# SCH_1-Up-Hackpad_2025-02-28.net
KiCad netlist of a schematic drawn in EasyEDA
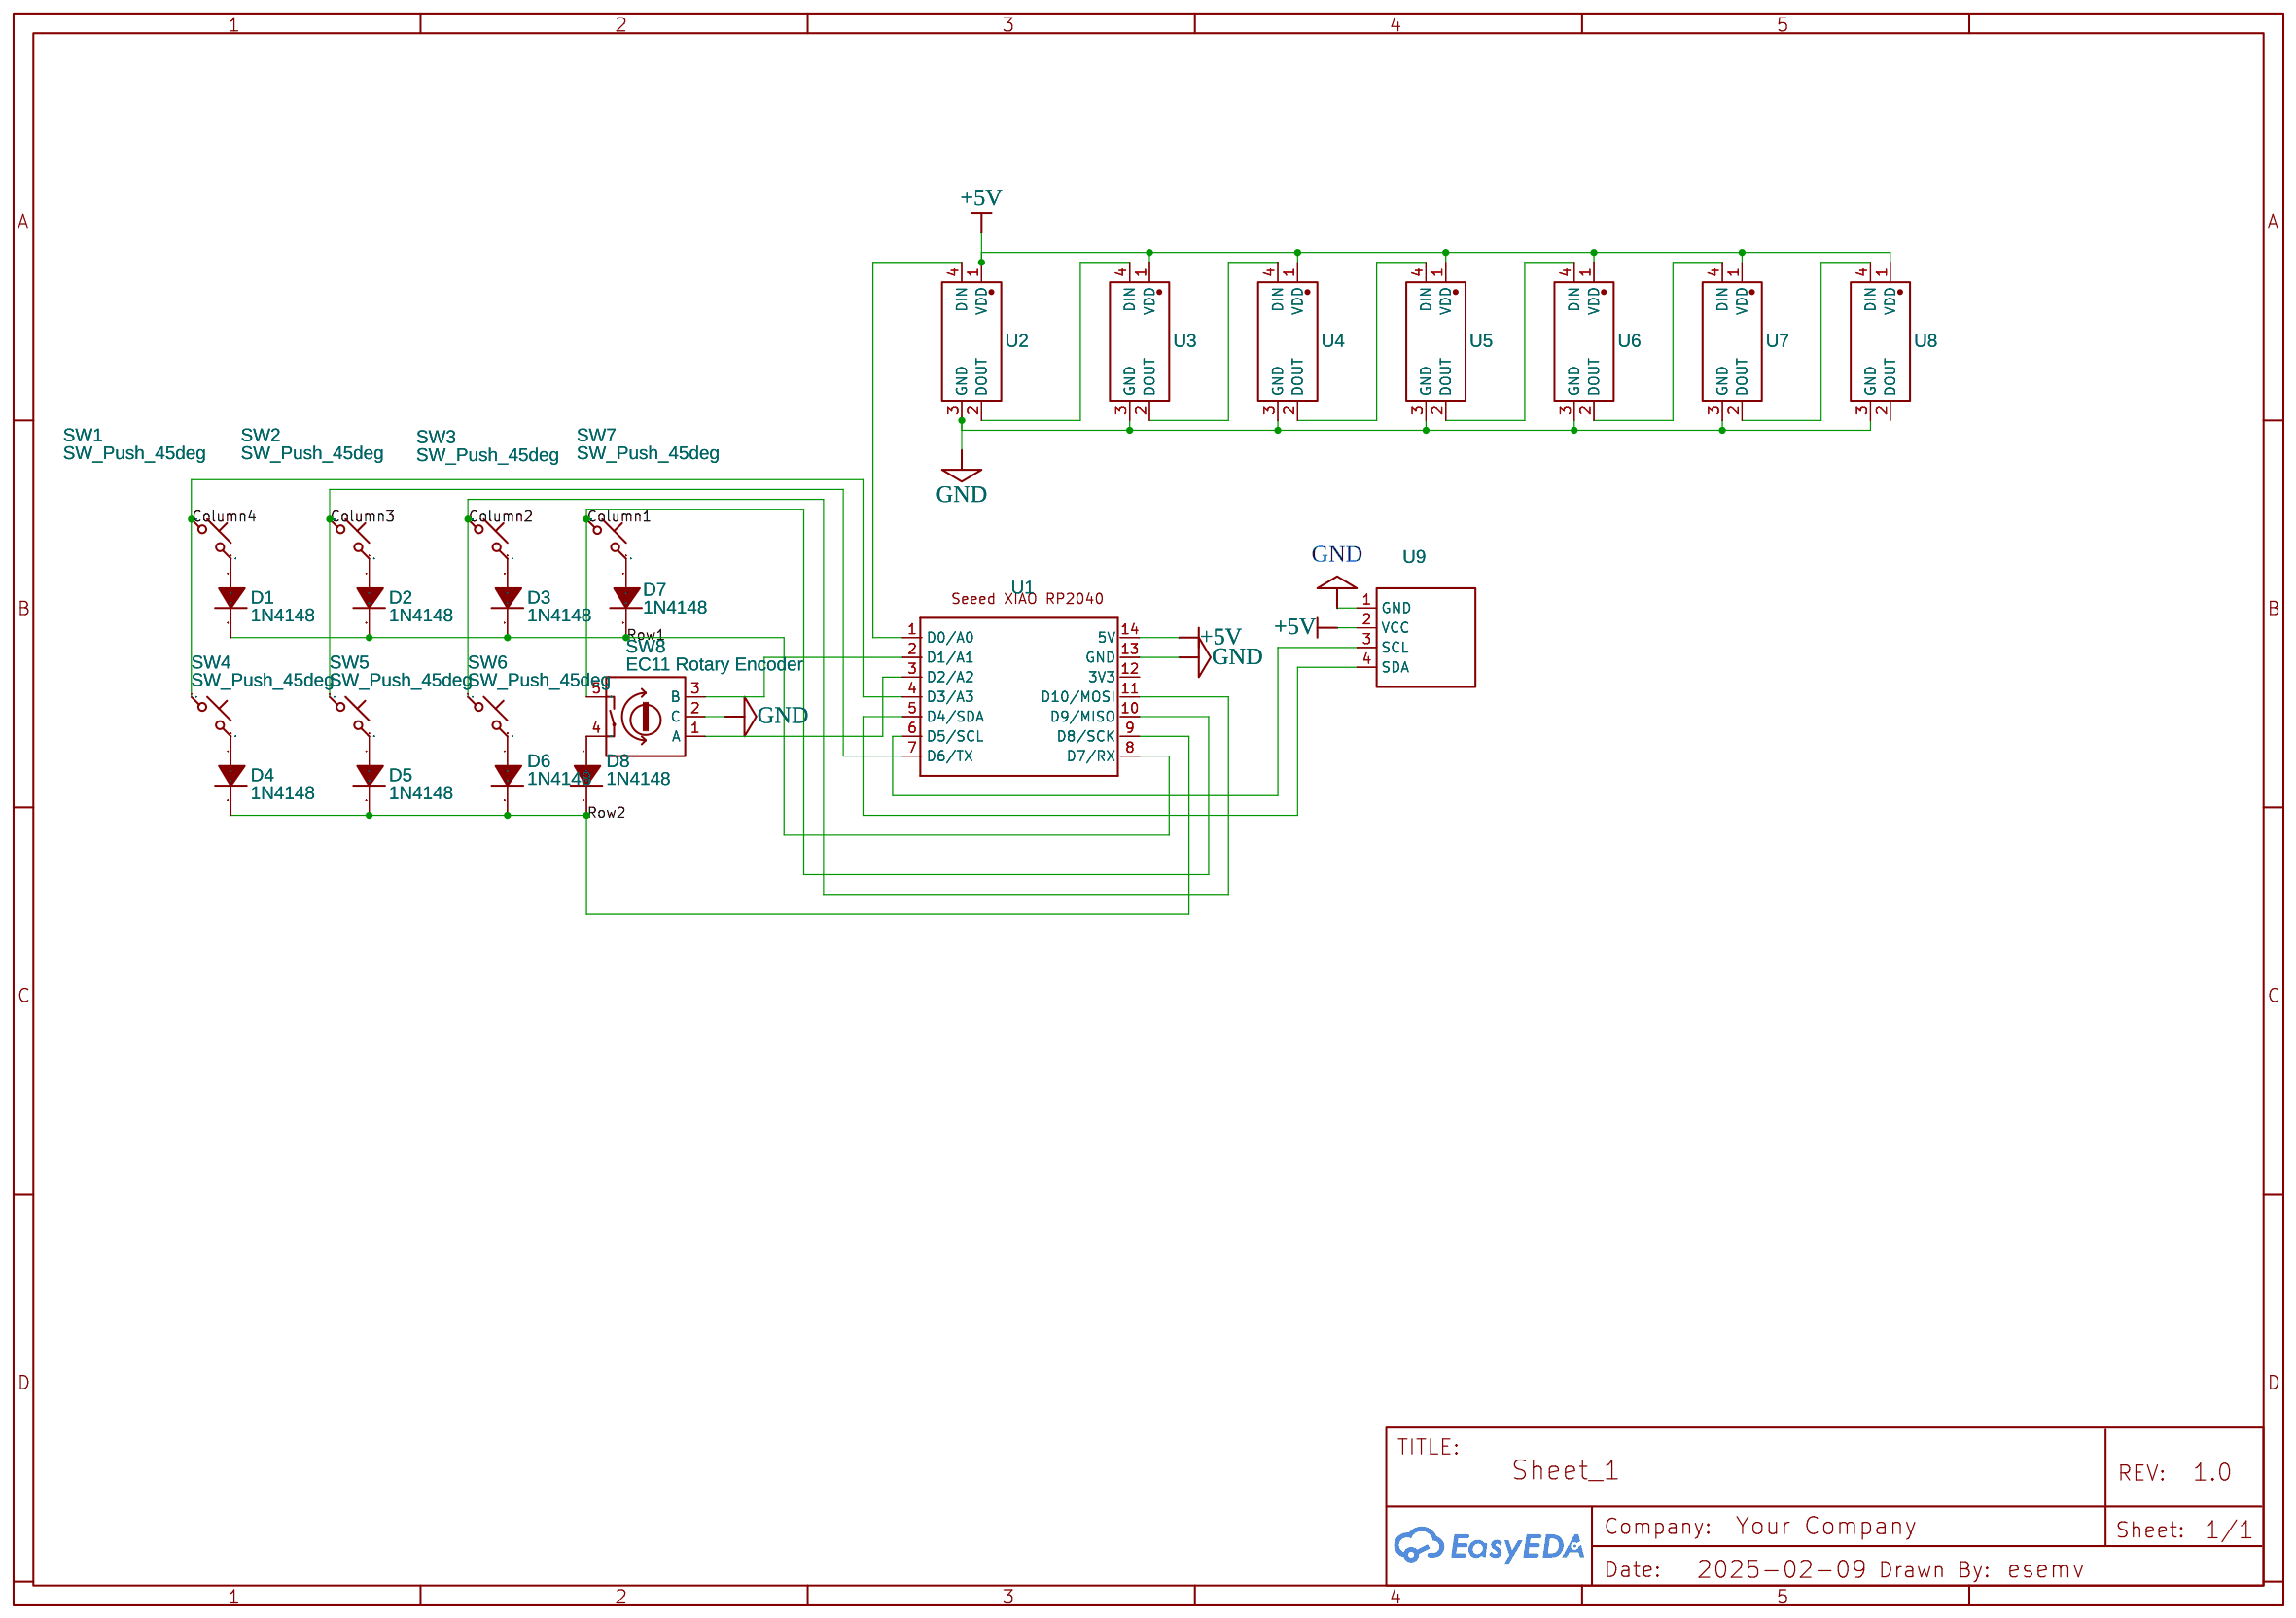
[diagram p0: schematic sheet]

(export (version "E")
  (design (tool "Eeschema 10.0.6"))
  (components
    (comp (ref "D1")
      (value "1N4148")
      (fields (field (name "Manufacturer") "ST(先科)"))
      (libsource (lib "") (part "1N4148"))
    )
    (comp (ref "D2")
      (value "1N4148")
      (fields (field (name "Manufacturer") "ST(先科)"))
      (libsource (lib "") (part "1N4148"))
    )
    (comp (ref "D3")
      (value "1N4148")
      (fields (field (name "Manufacturer") "ST(先科)"))
      (libsource (lib "") (part "1N4148"))
    )
    (comp (ref "D4")
      (value "1N4148")
      (fields (field (name "Manufacturer") "ST(先科)"))
      (libsource (lib "") (part "1N4148"))
    )
    (comp (ref "D5")
      (value "1N4148")
      (fields (field (name "Manufacturer") "ST(先科)"))
      (libsource (lib "") (part "1N4148"))
    )
    (comp (ref "D6")
      (value "1N4148")
      (fields (field (name "Manufacturer") "ST(先科)"))
      (libsource (lib "") (part "1N4148"))
    )
    (comp (ref "D7")
      (value "1N4148")
      (fields (field (name "Manufacturer") "ST(先科)"))
      (libsource (lib "") (part "1N4148"))
    )
    (comp (ref "D8")
      (value "1N4148")
      (fields (field (name "Manufacturer") "ST(先科)"))
      (libsource (lib "") (part "1N4148"))
    )
    (comp (ref "SW1") (value "SW_Push_45deg") (libsource (lib "") (part "SW_Push_45deg_1")))
    (comp (ref "SW2") (value "SW_Push_45deg") (libsource (lib "") (part "SW_Push_45deg_1")))
    (comp (ref "SW3") (value "SW_Push_45deg") (libsource (lib "") (part "SW_Push_45deg_1")))
    (comp (ref "SW4") (value "SW_Push_45deg") (libsource (lib "") (part "SW_Push_45deg")))
    (comp (ref "SW5") (value "SW_Push_45deg") (libsource (lib "") (part "SW_Push_45deg")))
    (comp (ref "SW6") (value "SW_Push_45deg") (libsource (lib "") (part "SW_Push_45deg")))
    (comp (ref "SW7") (value "SW_Push_45deg") (libsource (lib "") (part "SW_Push_45deg_2")))
    (comp (ref "SW8") (value "EC11 Rotary Encoder") (libsource (lib "") (part "EC11 Rotary Encoder")))
    (comp (ref "U1") (value "NO") (libsource (lib "") (part "SEEED_XIAO_RP2040_HOLE")))
    (comp (ref "U2")
      (value "NO")
      (fields (field (name "Manufacturer Part") "SK6812MINI-E"))
      (libsource (lib "") (part "NEOPIXEL_SK6812MINI-E"))
    )
    (comp (ref "U3")
      (value "NO")
      (fields (field (name "Manufacturer Part") "SK6812MINI-E"))
      (libsource (lib "") (part "NEOPIXEL_SK6812MINI-E"))
    )
    (comp (ref "U4")
      (value "NO")
      (fields (field (name "Manufacturer Part") "SK6812MINI-E"))
      (libsource (lib "") (part "NEOPIXEL_SK6812MINI-E"))
    )
    (comp (ref "U5")
      (value "NO")
      (fields (field (name "Manufacturer Part") "SK6812MINI-E"))
      (libsource (lib "") (part "NEOPIXEL_SK6812MINI-E"))
    )
    (comp (ref "U6")
      (value "NO")
      (fields (field (name "Manufacturer Part") "SK6812MINI-E"))
      (libsource (lib "") (part "NEOPIXEL_SK6812MINI-E"))
    )
    (comp (ref "U7")
      (value "NO")
      (fields (field (name "Manufacturer Part") "SK6812MINI-E"))
      (libsource (lib "") (part "NEOPIXEL_SK6812MINI-E"))
    )
    (comp (ref "U8")
      (value "NO")
      (fields (field (name "Manufacturer Part") "SK6812MINI-E"))
      (libsource (lib "") (part "NEOPIXEL_SK6812MINI-E"))
    )
    (comp (ref "U9") (value "NO") (libsource (lib "") (part "JM SSD1306-128X32-OLED-0.91")))
  )
  (nets
    (net (code "1") (name "+5V") (class "Default")
      (node (ref "U1") (pin "14") (pinfunction "5V_14") (pintype "bidirectional"))
      (node (ref "U2") (pin "1") (pinfunction "VDD_1") (pintype "unspecified"))
      (node (ref "U3") (pin "1") (pinfunction "VDD_1") (pintype "unspecified"))
      (node (ref "U4") (pin "1") (pinfunction "VDD_1") (pintype "unspecified"))
      (node (ref "U5") (pin "1") (pinfunction "VDD_1") (pintype "unspecified"))
      (node (ref "U6") (pin "1") (pinfunction "VDD_1") (pintype "unspecified"))
      (node (ref "U7") (pin "1") (pinfunction "VDD_1") (pintype "unspecified"))
      (node (ref "U8") (pin "1") (pinfunction "VDD_1") (pintype "unspecified"))
      (node (ref "U9") (pin "2") (pinfunction "VCC_2") (pintype "input"))
    )
    (net (code "2") (name "/Column1") (class "Default")
      (node (ref "SW7") (pin "1") (pinfunction "1_1") (pintype "unspecified"))
      (node (ref "SW8") (pin "5") (pinfunction "Sw2_5") (pintype "input"))
      (node (ref "U1") (pin "10") (pinfunction "D9/MISO_10") (pintype "bidirectional"))
    )
    (net (code "3") (name "/Column2") (class "Default")
      (node (ref "SW3") (pin "1") (pinfunction "1_1") (pintype "unspecified"))
      (node (ref "SW6") (pin "1") (pinfunction "1_1") (pintype "unspecified"))
      (node (ref "U1") (pin "11") (pinfunction "D10/MOSI_11") (pintype "bidirectional"))
    )
    (net (code "4") (name "/Column3") (class "Default")
      (node (ref "SW2") (pin "1") (pinfunction "1_1") (pintype "unspecified"))
      (node (ref "SW5") (pin "1") (pinfunction "1_1") (pintype "unspecified"))
      (node (ref "U1") (pin "7") (pinfunction "D6/TX_7") (pintype "bidirectional"))
    )
    (net (code "5") (name "/Column4") (class "Default")
      (node (ref "SW1") (pin "1") (pinfunction "1_1") (pintype "unspecified"))
      (node (ref "SW4") (pin "1") (pinfunction "1_1") (pintype "unspecified"))
      (node (ref "U1") (pin "4") (pinfunction "D3/A3_4") (pintype "bidirectional"))
    )
    (net (code "6") (name "/Row1") (class "Default")
      (node (ref "D1") (pin "2") (pinfunction "C_2") (pintype "unspecified"))
      (node (ref "D2") (pin "2") (pinfunction "C_2") (pintype "unspecified"))
      (node (ref "D3") (pin "2") (pinfunction "C_2") (pintype "unspecified"))
      (node (ref "D7") (pin "2") (pinfunction "C_2") (pintype "unspecified"))
      (node (ref "U1") (pin "8") (pinfunction "D7/RX_8") (pintype "bidirectional"))
    )
    (net (code "7") (name "/Row2") (class "Default")
      (node (ref "D4") (pin "2") (pinfunction "C_2") (pintype "unspecified"))
      (node (ref "D5") (pin "2") (pinfunction "C_2") (pintype "unspecified"))
      (node (ref "D6") (pin "2") (pinfunction "C_2") (pintype "unspecified"))
      (node (ref "D8") (pin "2") (pinfunction "C_2") (pintype "unspecified"))
      (node (ref "U1") (pin "9") (pinfunction "D8/SCK_9") (pintype "bidirectional"))
    )
    (net (code "8") (name "GND") (class "Default")
      (node (ref "SW8") (pin "2") (pinfunction "C_2") (pintype "input"))
      (node (ref "U1") (pin "13") (pinfunction "GND_13") (pintype "bidirectional"))
      (node (ref "U2") (pin "3") (pinfunction "GND_3") (pintype "unspecified"))
      (node (ref "U3") (pin "3") (pinfunction "GND_3") (pintype "unspecified"))
      (node (ref "U4") (pin "3") (pinfunction "GND_3") (pintype "unspecified"))
      (node (ref "U5") (pin "3") (pinfunction "GND_3") (pintype "unspecified"))
      (node (ref "U6") (pin "3") (pinfunction "GND_3") (pintype "unspecified"))
      (node (ref "U7") (pin "3") (pinfunction "GND_3") (pintype "unspecified"))
      (node (ref "U8") (pin "3") (pinfunction "GND_3") (pintype "unspecified"))
      (node (ref "U9") (pin "1") (pinfunction "GND_1") (pintype "input"))
    )
    (net (code "9") (name "Net-(D1-A)") (class "Default")
      (node (ref "D1") (pin "1") (pinfunction "A_1") (pintype "unspecified"))
      (node (ref "SW1") (pin "2") (pinfunction "2_2") (pintype "unspecified"))
    )
    (net (code "10") (name "Net-(D2-A)") (class "Default")
      (node (ref "D2") (pin "1") (pinfunction "A_1") (pintype "unspecified"))
      (node (ref "SW2") (pin "2") (pinfunction "2_2") (pintype "unspecified"))
    )
    (net (code "11") (name "Net-(D3-A)") (class "Default")
      (node (ref "D3") (pin "1") (pinfunction "A_1") (pintype "unspecified"))
      (node (ref "SW3") (pin "2") (pinfunction "2_2") (pintype "unspecified"))
    )
    (net (code "12") (name "Net-(D4-A)") (class "Default")
      (node (ref "D4") (pin "1") (pinfunction "A_1") (pintype "unspecified"))
      (node (ref "SW4") (pin "2") (pinfunction "2_2") (pintype "unspecified"))
    )
    (net (code "13") (name "Net-(D5-A)") (class "Default")
      (node (ref "D5") (pin "1") (pinfunction "A_1") (pintype "unspecified"))
      (node (ref "SW5") (pin "2") (pinfunction "2_2") (pintype "unspecified"))
    )
    (net (code "14") (name "Net-(D6-A)") (class "Default")
      (node (ref "D6") (pin "1") (pinfunction "A_1") (pintype "unspecified"))
      (node (ref "SW6") (pin "2") (pinfunction "2_2") (pintype "unspecified"))
    )
    (net (code "15") (name "Net-(D7-A)") (class "Default")
      (node (ref "D7") (pin "1") (pinfunction "A_1") (pintype "unspecified"))
      (node (ref "SW7") (pin "2") (pinfunction "2_2") (pintype "unspecified"))
    )
    (net (code "16") (name "Net-(D8-A)") (class "Default")
      (node (ref "D8") (pin "1") (pinfunction "A_1") (pintype "unspecified"))
      (node (ref "SW8") (pin "4") (pinfunction "Sw1_4") (pintype "input"))
    )
    (net (code "17") (name "Net-(SW8-A)") (class "Default")
      (node (ref "SW8") (pin "1") (pinfunction "A_1") (pintype "input"))
      (node (ref "U1") (pin "3") (pinfunction "D2/A2_3") (pintype "bidirectional"))
    )
    (net (code "18") (name "Net-(SW8-B)") (class "Default")
      (node (ref "SW8") (pin "3") (pinfunction "B_3") (pintype "input"))
      (node (ref "U1") (pin "2") (pinfunction "D1/A1_2") (pintype "bidirectional"))
    )
    (net (code "19") (name "Net-(U1-D0{slash}A0)") (class "Default")
      (node (ref "U1") (pin "1") (pinfunction "D0/A0_1") (pintype "bidirectional"))
      (node (ref "U2") (pin "4") (pinfunction "DIN_4") (pintype "unspecified"))
    )
    (net (code "20") (name "Net-(U1-D4{slash}SDA)") (class "Default")
      (node (ref "U1") (pin "5") (pinfunction "D4/SDA_5") (pintype "bidirectional"))
      (node (ref "U9") (pin "4") (pinfunction "SDA_4") (pintype "passive"))
    )
    (net (code "21") (name "Net-(U1-D5{slash}SCL)") (class "Default")
      (node (ref "U1") (pin "6") (pinfunction "D5/SCL_6") (pintype "bidirectional"))
      (node (ref "U9") (pin "3") (pinfunction "SCL_3") (pintype "passive"))
    )
    (net (code "22") (name "Net-(U2-DOUT)") (class "Default")
      (node (ref "U2") (pin "2") (pinfunction "DOUT_2") (pintype "unspecified"))
      (node (ref "U3") (pin "4") (pinfunction "DIN_4") (pintype "unspecified"))
    )
    (net (code "23") (name "Net-(U3-DOUT)") (class "Default")
      (node (ref "U3") (pin "2") (pinfunction "DOUT_2") (pintype "unspecified"))
      (node (ref "U4") (pin "4") (pinfunction "DIN_4") (pintype "unspecified"))
    )
    (net (code "24") (name "Net-(U4-DOUT)") (class "Default")
      (node (ref "U4") (pin "2") (pinfunction "DOUT_2") (pintype "unspecified"))
      (node (ref "U5") (pin "4") (pinfunction "DIN_4") (pintype "unspecified"))
    )
    (net (code "25") (name "Net-(U5-DOUT)") (class "Default")
      (node (ref "U5") (pin "2") (pinfunction "DOUT_2") (pintype "unspecified"))
      (node (ref "U6") (pin "4") (pinfunction "DIN_4") (pintype "unspecified"))
    )
    (net (code "26") (name "Net-(U6-DOUT)") (class "Default")
      (node (ref "U6") (pin "2") (pinfunction "DOUT_2") (pintype "unspecified"))
      (node (ref "U7") (pin "4") (pinfunction "DIN_4") (pintype "unspecified"))
    )
    (net (code "27") (name "Net-(U7-DOUT)") (class "Default")
      (node (ref "U7") (pin "2") (pinfunction "DOUT_2") (pintype "unspecified"))
      (node (ref "U8") (pin "4") (pinfunction "DIN_4") (pintype "unspecified"))
    )
    (net (code "28") (name "unconnected-(U1-3V3-Pad12)") (class "Default")
      (node (ref "U1") (pin "12") (pinfunction "3V3_12") (pintype "bidirectional"))
    )
    (net (code "29") (name "unconnected-(U8-DOUT-Pad2)") (class "Default")
      (node (ref "U8") (pin "2") (pinfunction "DOUT_2") (pintype "unspecified"))
    )
  )
)
